# Sheet.net
KiCad netlist of a schematic drawn in Altium Designer
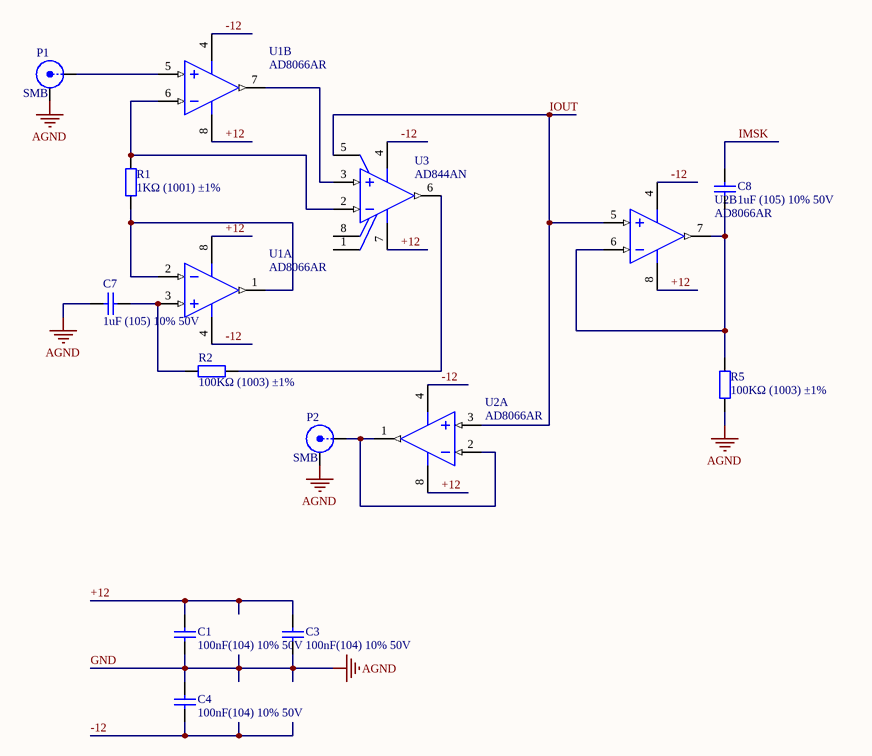
[diagram p0: Sheet.SchDoc]

(export (version "E")
  (design (tool "Eeschema 10.0.6"))
  (components
    (comp (ref "C1")
      (value "100nF(104) 10% 50V")
      (footprint "LC-0805_C")
      (description "贴片电容")
      (libsource (lib "Miscellaneous Devices LC") (part "0805 100nF(104) 10% 50V"))
    )
    (comp (ref "C3")
      (value "100nF(104) 10% 50V")
      (footprint "LC-0805_C")
      (description "贴片电容")
      (libsource (lib "Miscellaneous Devices LC") (part "0805 100nF(104) 10% 50V"))
    )
    (comp (ref "C4")
      (value "100nF(104) 10% 50V")
      (footprint "LC-0805_C")
      (description "贴片电容")
      (libsource (lib "Miscellaneous Devices LC") (part "0805 100nF(104) 10% 50V"))
    )
    (comp (ref "C7")
      (value "1uF (105) 10% 50V")
      (footprint "LC-0805_C")
      (description "贴片电容")
      (libsource (lib "Miscellaneous Devices LC") (part "0805 1uF (105) 10% 50V"))
    )
    (comp (ref "C8")
      (value "1uF (105) 10% 50V")
      (footprint "LC-0805_C")
      (description "贴片电容")
      (libsource (lib "Miscellaneous Devices LC") (part "0805 1uF (105) 10% 50V"))
    )
    (comp (ref "P1")
      (value "SMB")
      (footprint "SMB_V-RJ45")
      (description "SMB Straight Connector")
      (fields (field (name "PUBLISHER") "Altium Limited"))
      (libsource (lib "Miscellaneous Connectors") (part "SMB"))
    )
    (comp (ref "P2")
      (value "SMB")
      (footprint "SMB_V-RJ45")
      (description "SMB Straight Connector")
      (fields (field (name "PUBLISHER") "Altium Limited"))
      (libsource (lib "Miscellaneous Connectors") (part "SMB"))
    )
    (comp (ref "R1")
      (value "1KΩ (1001) ±1%")
      (footprint "LC-0805_R")
      (description "贴片电阻")
      (libsource (lib "Miscellaneous Devices LC") (part "0805 1KΩ (1001) 1%"))
    )
    (comp (ref "R2")
      (value "100KΩ (1003) ±1%")
      (footprint "LC-0805_R")
      (description "贴片电阻")
      (libsource (lib "Miscellaneous Devices LC") (part "0805 100KΩ (1003) 1%"))
    )
    (comp (ref "R5")
      (value "100KΩ (1003) ±1%")
      (footprint "LC-0805_R")
      (description "贴片电阻")
      (libsource (lib "") (part "0805 100KΩ (1003) 1%_1"))
    )
    (comp (ref "U1")
      (value "AD8066AR")
      (footprint "ADI-R-8_N")
      (fields (field (name "GENERIC PART NUMBER") "AD8066") (field (name "MANUFACTURER") "Analog Devices"))
      (libsource (lib "Analog Devices Operational Amplifiers") (part "AD8066AR"))
    )
    (comp (ref "U2")
      (value "AD8066AR")
      (footprint "ADI-R-8_N")
      (fields (field (name "GENERIC PART NUMBER") "AD8066") (field (name "MANUFACTURER") "Analog Devices"))
      (libsource (lib "Analog Devices Operational Amplifiers") (part "AD8066AR"))
    )
    (comp (ref "U3")
      (value "AD844AN")
      (footprint "ADI-N-8")
      (fields (field (name "GENERIC PART NUMBER") "AD844") (field (name "MANUFACTURER") "Analog Devices"))
      (libsource (lib "Analog Devices Operational Amplifiers") (part "AD844AN"))
    )
  )
  (nets
    (net (code "1") (name "/+12") (class "Default")
      (node (ref "C1") (pin "2") (pinfunction "2_2") (pintype "passive"))
      (node (ref "C3") (pin "2") (pinfunction "2_2") (pintype "passive"))
      (node (ref "U1") (pin "8") (pinfunction "+VS_8") (pintype "power_in"))
      (node (ref "U2") (pin "8") (pinfunction "+VS_8") (pintype "power_in"))
      (node (ref "U3") (pin "7") (pinfunction "+VS_7") (pintype "power_in"))
    )
    (net (code "2") (name "/-12") (class "Default")
      (node (ref "C4") (pin "1") (pinfunction "1_1") (pintype "passive"))
      (node (ref "U1") (pin "4") (pinfunction "-VS_4") (pintype "power_in"))
      (node (ref "U2") (pin "4") (pinfunction "-VS_4") (pintype "power_in"))
      (node (ref "U3") (pin "4") (pinfunction "-VS_4") (pintype "power_in"))
    )
    (net (code "3") (name "/IMSK") (class "Default")
      (node (ref "C8") (pin "2") (pinfunction "2_2") (pintype "passive"))
    )
    (net (code "4") (name "/IOUT") (class "Default")
      (node (ref "U2") (pin "3") (pinfunction "+IN_1_3") (pintype "input"))
      (node (ref "U2") (pin "5") (pinfunction "+IN_2_5") (pintype "input"))
      (node (ref "U3") (pin "5") (pinfunction "TZ_5") (pintype "passive"))
    )
    (net (code "5") (name "AGND") (class "Default")
      (node (ref "C1") (pin "1") (pinfunction "1_1") (pintype "passive"))
      (node (ref "C3") (pin "1") (pinfunction "1_1") (pintype "passive"))
      (node (ref "C4") (pin "2") (pinfunction "2_2") (pintype "passive"))
      (node (ref "C7") (pin "1") (pinfunction "1_1") (pintype "passive"))
      (node (ref "P1") (pin "2") (pinfunction "Y_2") (pintype "passive"))
      (node (ref "P2") (pin "2") (pinfunction "Y_2") (pintype "passive"))
      (node (ref "R5") (pin "1") (pinfunction "1_1") (pintype "passive"))
    )
    (net (code "6") (name "Net-(P1-X)") (class "Default")
      (node (ref "P1") (pin "1") (pinfunction "X_1") (pintype "passive"))
      (node (ref "U1") (pin "5") (pinfunction "+IN_2_5") (pintype "input"))
    )
    (net (code "7") (name "Net-(P2-X)") (class "Default")
      (node (ref "P2") (pin "1") (pinfunction "X_1") (pintype "passive"))
      (node (ref "U2") (pin "1") (pinfunction "VOUT_1_1") (pintype "output"))
      (node (ref "U2") (pin "2") (pinfunction "-IN_1_2") (pintype "input"))
    )
    (net (code "8") (name "Net-(U1A-+IN_1)") (class "Default")
      (node (ref "C7") (pin "2") (pinfunction "2_2") (pintype "passive"))
      (node (ref "R2") (pin "1") (pinfunction "1_1") (pintype "passive"))
      (node (ref "U1") (pin "3") (pinfunction "+IN_1_3") (pintype "input"))
    )
    (net (code "9") (name "Net-(U1A--IN_1)") (class "Default")
      (node (ref "R1") (pin "1") (pinfunction "1_1") (pintype "passive"))
      (node (ref "U1") (pin "1") (pinfunction "VOUT_1_1") (pintype "output"))
      (node (ref "U1") (pin "2") (pinfunction "-IN_1_2") (pintype "input"))
    )
    (net (code "10") (name "Net-(U1B--IN_2)") (class "Default")
      (node (ref "R1") (pin "2") (pinfunction "2_2") (pintype "passive"))
      (node (ref "U1") (pin "6") (pinfunction "-IN_2_6") (pintype "input"))
      (node (ref "U3") (pin "2") (pinfunction "-IN_2") (pintype "input"))
    )
    (net (code "11") (name "Net-(U1B-VOUT_2)") (class "Default")
      (node (ref "U1") (pin "7") (pinfunction "VOUT_2_7") (pintype "output"))
      (node (ref "U3") (pin "3") (pinfunction "+IN_3") (pintype "input"))
    )
    (net (code "12") (name "Net-(U2B--IN_2)") (class "Default")
      (node (ref "C8") (pin "1") (pinfunction "1_1") (pintype "passive"))
      (node (ref "R5") (pin "2") (pinfunction "2_2") (pintype "passive"))
      (node (ref "U2") (pin "6") (pinfunction "-IN_2_6") (pintype "input"))
      (node (ref "U2") (pin "7") (pinfunction "VOUT_2_7") (pintype "output"))
    )
    (net (code "13") (name "Net-(U3-OUTPUT)") (class "Default")
      (node (ref "R2") (pin "2") (pinfunction "2_2") (pintype "passive"))
      (node (ref "U3") (pin "6") (pinfunction "OUTPUT_6") (pintype "output"))
    )
    (net (code "14") (name "unconnected-(U3-NULL-Pad1)") (class "Default")
      (node (ref "U3") (pin "1") (pinfunction "NULL_1") (pintype "passive"))
    )
    (net (code "15") (name "unconnected-(U3-NULL-Pad8)") (class "Default")
      (node (ref "U3") (pin "8") (pinfunction "NULL_8") (pintype "passive"))
    )
  )
)
